# Schematique_TEST.net
KiCad netlist of a schematic drawn in EAGLE
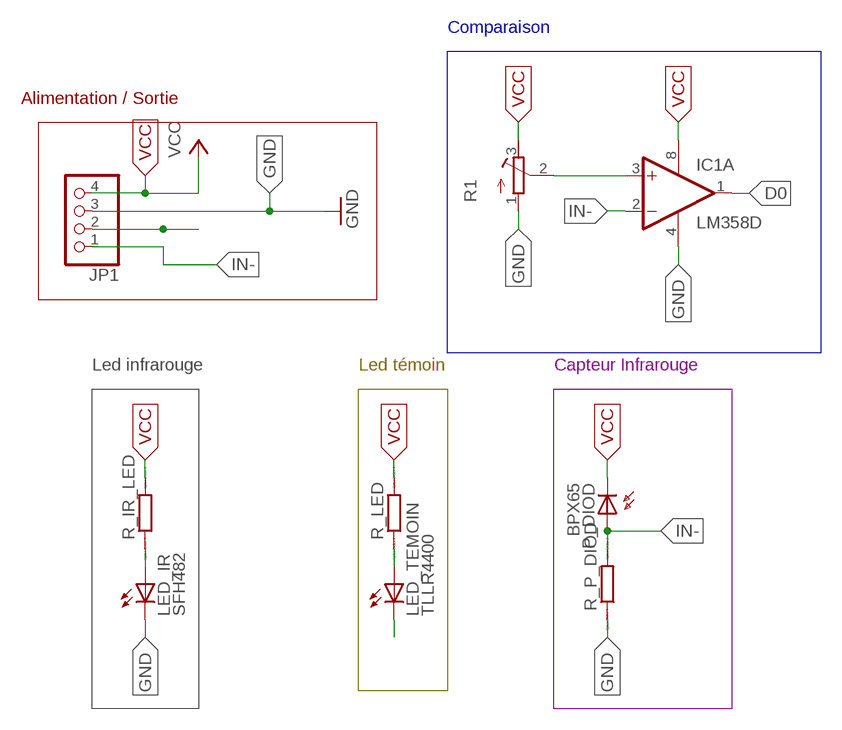
[diagram p0: schematic, sheet 1]

(export (version "E")
  (design (tool "Eeschema 10.0.6"))
  (components
    (comp (ref "IC1")
      (value "LM358D")
      (footprint "eagle-import:SO08")
      (libsource (lib "eagle-import") (part "LM358D"))
    )
    (comp (ref "JP1")
      (value "PINHD-1X4M")
      (footprint "eagle-import:1X04M")
      (libsource (lib "eagle-import") (part "PINHD-1X4M"))
    )
    (comp (ref "LED_IR")
      (value "SFH482")
      (footprint "eagle-import:SFH482")
      (libsource (lib "eagle-import") (part "SFH482"))
    )
    (comp (ref "LED_TEMOIN")
      (value "TLLR4400")
      (footprint "eagle-import:LED3MM")
      (fields (field (name "MF") "VISHAY SEMICONDUCTOR"))
      (libsource (lib "eagle-import") (part "TLLR4400"))
    )
    (comp (ref "P_DIOD")
      (value "BPX65")
      (footprint "eagle-import:BPX65")
      (fields (field (name "MPN") "BPX65."))
      (libsource (lib "eagle-import") (part "BPX65"))
    )
    (comp (ref "R1")
      (value "R-TRIMM4G/J")
      (footprint "eagle-import:RTRIM4G_J")
      (libsource (lib "eagle-import") (part "R-TRIMM4G/J"))
    )
    (comp (ref "R_IR_LED")
      (value "RR1206")
      (footprint "eagle-import:R1206")
      (libsource (lib "eagle-import") (part "RR1206"))
    )
    (comp (ref "R_LED")
      (value "RR1206")
      (footprint "eagle-import:R1206")
      (libsource (lib "eagle-import") (part "RR1206"))
    )
    (comp (ref "R_P_DIOD")
      (value "RR1206")
      (footprint "eagle-import:R1206")
      (libsource (lib "eagle-import") (part "RR1206"))
    )
  )
  (nets
    (net (code "1") (name "D0") (class "Default")
      (node (ref "IC1") (pin "1") (pinfunction "OUT_1") (pintype "output"))
      (node (ref "JP1") (pin "2") (pinfunction "2_2") (pintype "passive"))
      (node (ref "LED_TEMOIN") (pin "K") (pinfunction "C_K") (pintype "passive"))
    )
    (net (code "2") (name "GND") (class "Default")
      (node (ref "IC1") (pin "4") (pinfunction "V-_4") (pintype "power_in"))
      (node (ref "JP1") (pin "3") (pinfunction "3_3") (pintype "passive"))
      (node (ref "LED_IR") (pin "K") (pinfunction "C_K") (pintype "passive"))
      (node (ref "R1") (pin "1") (pinfunction "A_1") (pintype "passive"))
      (node (ref "R_P_DIOD") (pin "1") (pinfunction "1_1") (pintype "passive"))
    )
    (net (code "3") (name "IN-") (class "Default")
      (node (ref "IC1") (pin "2") (pinfunction "-IN_2") (pintype "input"))
      (node (ref "JP1") (pin "1") (pinfunction "1_1") (pintype "passive"))
      (node (ref "P_DIOD") (pin "A") (pinfunction "A_A") (pintype "passive"))
      (node (ref "R_P_DIOD") (pin "2") (pinfunction "2_2") (pintype "passive"))
    )
    (net (code "4") (name "Net-(IC1A-+IN)") (class "Default")
      (node (ref "IC1") (pin "3") (pinfunction "+IN_3") (pintype "input"))
      (node (ref "R1") (pin "2") (pinfunction "S_2") (pintype "passive"))
    )
    (net (code "5") (name "Net-(LED_IR-PadA)") (class "Default")
      (node (ref "LED_IR") (pin "A") (pinfunction "A_A") (pintype "passive"))
      (node (ref "R_IR_LED") (pin "1") (pinfunction "1_1") (pintype "passive"))
    )
    (net (code "6") (name "Net-(LED_TEMOIN-PadA)") (class "Default")
      (node (ref "LED_TEMOIN") (pin "A") (pinfunction "A_A") (pintype "passive"))
      (node (ref "R_LED") (pin "1") (pinfunction "1_1") (pintype "passive"))
    )
    (net (code "7") (name "VCC") (class "Default")
      (node (ref "IC1") (pin "8") (pinfunction "V+_8") (pintype "power_in"))
      (node (ref "JP1") (pin "4") (pinfunction "4_4") (pintype "passive"))
      (node (ref "P_DIOD") (pin "K") (pinfunction "C_K") (pintype "passive"))
      (node (ref "R1") (pin "3") (pinfunction "E_3") (pintype "passive"))
      (node (ref "R_IR_LED") (pin "2") (pinfunction "2_2") (pintype "passive"))
      (node (ref "R_LED") (pin "2") (pinfunction "2_2") (pintype "passive"))
    )
  )
)
